# Sheet1.net
KiCad netlist of a schematic drawn in Altium Designer
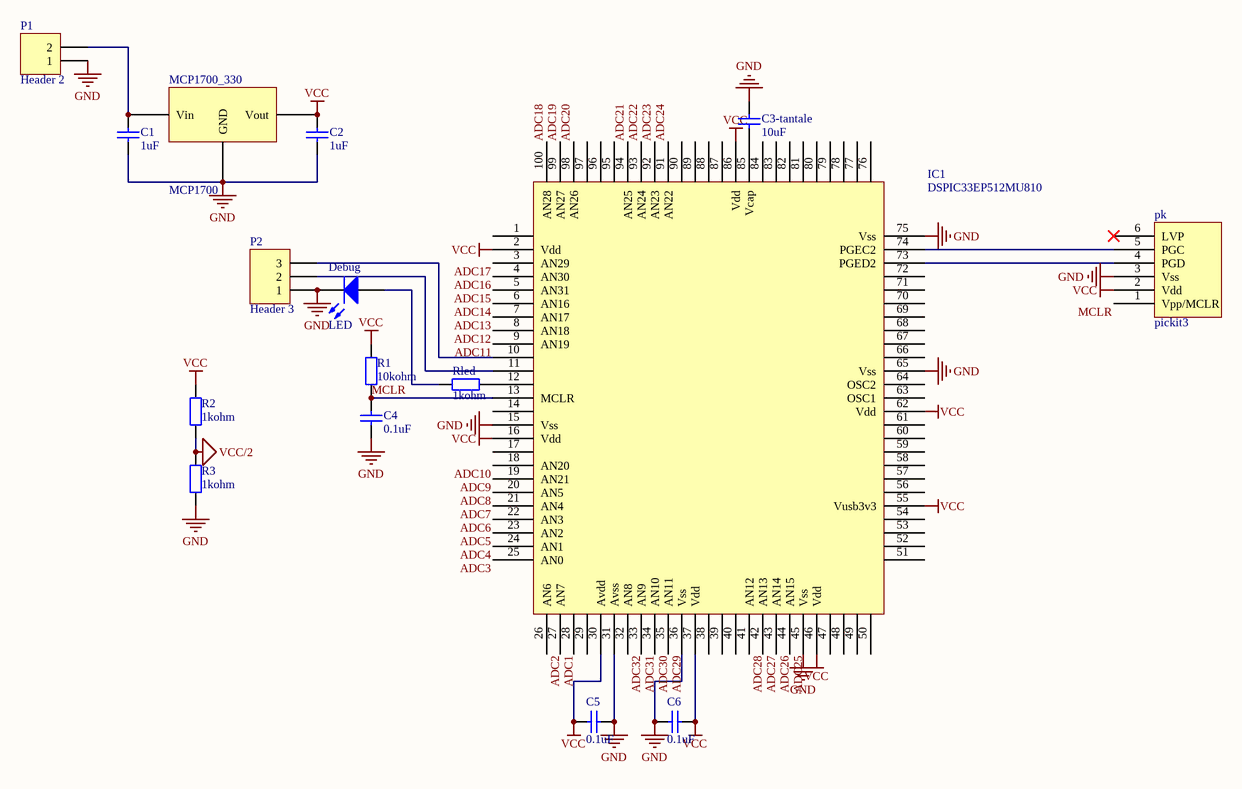
[diagram p0: Sheet1.SchDoc]

(export (version "E")
  (design (tool "Eeschema 10.0.6"))
  (components
    (comp (ref "C1")
      (value "1uF")
      (footprint "cms805 - mini")
      (libsource (lib "lib_Robotronik") (part "Capa"))
    )
    (comp (ref "C2")
      (value "1uF")
      (footprint "cms805 - mini")
      (libsource (lib "lib_Robotronik") (part "Capa"))
    )
    (comp (ref "C3-tantale")
      (value "10uF")
      (footprint "cms805")
      (libsource (lib "lib_Robotronik") (part "Capa"))
    )
    (comp (ref "C4")
      (value "0.1uF")
      (footprint "cms805 - mini")
      (libsource (lib "lib_Robotronik") (part "Capa"))
    )
    (comp (ref "C5")
      (value "0.1uF")
      (footprint "cms805 - mini")
      (libsource (lib "lib_Robotronik") (part "Capa"))
    )
    (comp (ref "C6")
      (value "0.1uF")
      (footprint "cms805 - mini")
      (libsource (lib "lib_Robotronik") (part "Capa"))
    )
    (comp (ref "Debug") (value "LED") (footprint "cms1206") (libsource (lib "lib_Robotronik") (part "LED")))
    (comp (ref "IC1")
      (value "DSPIC33EP512MU810")
      (footprint "TQFP100PF")
      (libsource (lib "lib_Robotronik") (part "DSPIC33EP512MU810"))
    )
    (comp (ref "MCP1700_330")
      (value "MCP1700")
      (footprint "SOT89")
      (libsource (lib "lib_Robotronik") (part "MCP1700"))
    )
    (comp (ref "P1")
      (value "Header 2")
      (footprint "HDR1X2")
      (description "Header, 2-Pin")
      (fields (field (name "PUBLISHER") "Altium Limited"))
      (libsource (lib "Miscellaneous Connectors") (part "Header 2"))
    )
    (comp (ref "P2")
      (value "Header 3")
      (footprint "HDR1X3")
      (description "Header, 3-Pin")
      (fields (field (name "PUBLISHER") "Altium Limited"))
      (libsource (lib "Miscellaneous Connectors") (part "Header 3"))
    )
    (comp (ref "pk")
      (value "pickit3")
      (footprint "pickit3")
      (libsource (lib "lib_Robotronik") (part "pickit3"))
    )
    (comp (ref "R1")
      (value "10kohm")
      (footprint "cms805 - mini")
      (libsource (lib "lib_Robotronik") (part "Resistance"))
    )
    (comp (ref "R2")
      (value "1kohm")
      (footprint "cms805 - mini")
      (libsource (lib "lib_Robotronik") (part "Resistance"))
    )
    (comp (ref "R3")
      (value "1kohm")
      (footprint "cms805 - mini")
      (libsource (lib "lib_Robotronik") (part "Resistance"))
    )
    (comp (ref "Rled") (value "1kohm") (footprint "cms805 - mini") (libsource (lib "") (part "Resistance_1")))
  )
  (nets
    (net (code "1") (name "/ADC1") (class "Default")
      (node (ref "IC1") (pin "27") (pinfunction "AN7_27") (pintype "passive"))
    )
    (net (code "2") (name "/ADC2") (class "Default")
      (node (ref "IC1") (pin "26") (pinfunction "AN6_26") (pintype "passive"))
    )
    (net (code "3") (name "/ADC3") (class "Default")
      (node (ref "IC1") (pin "25") (pinfunction "AN0_25") (pintype "passive"))
    )
    (net (code "4") (name "/ADC4") (class "Default")
      (node (ref "IC1") (pin "24") (pinfunction "AN1_24") (pintype "passive"))
    )
    (net (code "5") (name "/ADC5") (class "Default")
      (node (ref "IC1") (pin "23") (pinfunction "AN2_23") (pintype "passive"))
    )
    (net (code "6") (name "/ADC6") (class "Default")
      (node (ref "IC1") (pin "22") (pinfunction "AN3_22") (pintype "passive"))
    )
    (net (code "7") (name "/ADC7") (class "Default")
      (node (ref "IC1") (pin "21") (pinfunction "AN4_21") (pintype "passive"))
    )
    (net (code "8") (name "/ADC8") (class "Default")
      (node (ref "IC1") (pin "20") (pinfunction "AN5_20") (pintype "passive"))
    )
    (net (code "9") (name "/ADC9") (class "Default")
      (node (ref "IC1") (pin "19") (pinfunction "AN21_19") (pintype "passive"))
    )
    (net (code "10") (name "/ADC10") (class "Default")
      (node (ref "IC1") (pin "18") (pinfunction "AN20_18") (pintype "passive"))
    )
    (net (code "11") (name "/ADC11") (class "Default")
      (node (ref "IC1") (pin "9") (pinfunction "AN19_9") (pintype "passive"))
    )
    (net (code "12") (name "/ADC12") (class "Default")
      (node (ref "IC1") (pin "8") (pinfunction "AN18_8") (pintype "passive"))
    )
    (net (code "13") (name "/ADC13") (class "Default")
      (node (ref "IC1") (pin "7") (pinfunction "AN17_7") (pintype "passive"))
    )
    (net (code "14") (name "/ADC14") (class "Default")
      (node (ref "IC1") (pin "6") (pinfunction "AN16_6") (pintype "passive"))
    )
    (net (code "15") (name "/ADC15") (class "Default")
      (node (ref "IC1") (pin "5") (pinfunction "AN31_5") (pintype "passive"))
    )
    (net (code "16") (name "/ADC16") (class "Default")
      (node (ref "IC1") (pin "4") (pinfunction "AN30_4") (pintype "passive"))
    )
    (net (code "17") (name "/ADC17") (class "Default")
      (node (ref "IC1") (pin "3") (pinfunction "AN29_3") (pintype "passive"))
    )
    (net (code "18") (name "/ADC18") (class "Default")
      (node (ref "IC1") (pin "100") (pinfunction "AN28_100") (pintype "passive"))
    )
    (net (code "19") (name "/ADC19") (class "Default")
      (node (ref "IC1") (pin "99") (pinfunction "AN27_99") (pintype "passive"))
    )
    (net (code "20") (name "/ADC20") (class "Default")
      (node (ref "IC1") (pin "98") (pinfunction "AN26_98") (pintype "passive"))
    )
    (net (code "21") (name "/ADC21") (class "Default")
      (node (ref "IC1") (pin "94") (pinfunction "AN25_94") (pintype "passive"))
    )
    (net (code "22") (name "/ADC22") (class "Default")
      (node (ref "IC1") (pin "93") (pinfunction "AN24_93") (pintype "passive"))
    )
    (net (code "23") (name "/ADC23") (class "Default")
      (node (ref "IC1") (pin "92") (pinfunction "AN23_92") (pintype "passive"))
    )
    (net (code "24") (name "/ADC24") (class "Default")
      (node (ref "IC1") (pin "91") (pinfunction "AN22_91") (pintype "passive"))
    )
    (net (code "25") (name "/ADC25") (class "Default")
      (node (ref "IC1") (pin "44") (pinfunction "AN15_44") (pintype "passive"))
    )
    (net (code "26") (name "/ADC26") (class "Default")
      (node (ref "IC1") (pin "43") (pinfunction "AN14_43") (pintype "passive"))
    )
    (net (code "27") (name "/ADC27") (class "Default")
      (node (ref "IC1") (pin "42") (pinfunction "AN13_42") (pintype "passive"))
    )
    (net (code "28") (name "/ADC28") (class "Default")
      (node (ref "IC1") (pin "41") (pinfunction "AN12_41") (pintype "passive"))
    )
    (net (code "29") (name "/ADC29") (class "Default")
      (node (ref "IC1") (pin "35") (pinfunction "AN11_35") (pintype "passive"))
    )
    (net (code "30") (name "/ADC30") (class "Default")
      (node (ref "IC1") (pin "34") (pinfunction "AN10_34") (pintype "passive"))
    )
    (net (code "31") (name "/ADC31") (class "Default")
      (node (ref "IC1") (pin "33") (pinfunction "AN9_33") (pintype "passive"))
    )
    (net (code "32") (name "/ADC32") (class "Default")
      (node (ref "IC1") (pin "32") (pinfunction "AN8_32") (pintype "passive"))
    )
    (net (code "33") (name "/MCLR") (class "Default")
      (node (ref "C4") (pin "2") (pinfunction "2_2") (pintype "passive"))
      (node (ref "IC1") (pin "13") (pinfunction "MCLR_13") (pintype "passive"))
      (node (ref "R1") (pin "1") (pinfunction "1_1") (pintype "passive"))
      (node (ref "pk") (pin "1") (pinfunction "Vpp/MCLR_1") (pintype "passive"))
    )
    (net (code "34") (name "GND") (class "Default")
      (node (ref "C1") (pin "1") (pinfunction "1_1") (pintype "passive"))
      (node (ref "C2") (pin "1") (pinfunction "1_1") (pintype "passive"))
      (node (ref "C3-tantale") (pin "2") (pinfunction "2_2") (pintype "passive"))
      (node (ref "C4") (pin "1") (pinfunction "1_1") (pintype "passive"))
      (node (ref "C5") (pin "1") (pinfunction "1_1") (pintype "passive"))
      (node (ref "C6") (pin "2") (pinfunction "2_2") (pintype "passive"))
      (node (ref "Debug") (pin "2") (pinfunction "K_2") (pintype "passive"))
      (node (ref "IC1") (pin "15") (pinfunction "Vss_15") (pintype "passive"))
      (node (ref "IC1") (pin "31") (pinfunction "Avss_31") (pintype "passive"))
      (node (ref "IC1") (pin "36") (pinfunction "Vss_36") (pintype "passive"))
      (node (ref "IC1") (pin "45") (pinfunction "Vss_45") (pintype "passive"))
      (node (ref "IC1") (pin "65") (pinfunction "Vss_65") (pintype "passive"))
      (node (ref "IC1") (pin "75") (pinfunction "Vss_75") (pintype "passive"))
      (node (ref "MCP1700_330") (pin "1") (pinfunction "GND_1") (pintype "passive"))
      (node (ref "P1") (pin "1") (pinfunction "1_1") (pintype "passive"))
      (node (ref "P2") (pin "1") (pinfunction "1_1") (pintype "passive"))
      (node (ref "R3") (pin "1") (pinfunction "1_1") (pintype "passive"))
      (node (ref "pk") (pin "3") (pinfunction "Vss_3") (pintype "passive"))
    )
    (net (code "35") (name "Net-(Debug-A)") (class "Default")
      (node (ref "Debug") (pin "1") (pinfunction "A_1") (pintype "passive"))
      (node (ref "Rled") (pin "2") (pinfunction "2_2") (pintype "passive"))
    )
    (net (code "36") (name "Net-(IC1-PGEC2)") (class "Default")
      (node (ref "IC1") (pin "74") (pinfunction "PGEC2_74") (pintype "passive"))
      (node (ref "pk") (pin "5") (pinfunction "PGC_5") (pintype "passive"))
    )
    (net (code "37") (name "Net-(IC1-PGED2)") (class "Default")
      (node (ref "IC1") (pin "73") (pinfunction "PGED2_73") (pintype "passive"))
      (node (ref "pk") (pin "4") (pinfunction "PGD_4") (pintype "passive"))
    )
    (net (code "38") (name "Net-(IC1-Pad10)") (class "Default")
      (node (ref "IC1") (pin "10") (pintype "passive"))
      (node (ref "P2") (pin "3") (pinfunction "3_3") (pintype "passive"))
    )
    (net (code "39") (name "Net-(IC1-Pad11)") (class "Default")
      (node (ref "IC1") (pin "11") (pintype "passive"))
      (node (ref "P2") (pin "2") (pinfunction "2_2") (pintype "passive"))
    )
    (net (code "40") (name "Net-(IC1-Pad12)") (class "Default")
      (node (ref "IC1") (pin "12") (pintype "passive"))
      (node (ref "Rled") (pin "1") (pinfunction "1_1") (pintype "passive"))
    )
    (net (code "41") (name "Net-(IC1-Vcap)") (class "Default")
      (node (ref "C3-tantale") (pin "1") (pinfunction "1_1") (pintype "passive"))
      (node (ref "IC1") (pin "85") (pinfunction "Vcap_85") (pintype "passive"))
    )
    (net (code "42") (name "Net-(MCP1700_330-Vin)") (class "Default")
      (node (ref "C1") (pin "2") (pinfunction "2_2") (pintype "passive"))
      (node (ref "MCP1700_330") (pin "2") (pinfunction "Vin_2") (pintype "passive"))
      (node (ref "P1") (pin "2") (pinfunction "2_2") (pintype "passive"))
    )
    (net (code "43") (name "VCC") (class "Default")
      (node (ref "C2") (pin "2") (pinfunction "2_2") (pintype "passive"))
      (node (ref "C5") (pin "2") (pinfunction "2_2") (pintype "passive"))
      (node (ref "C6") (pin "1") (pinfunction "1_1") (pintype "passive"))
      (node (ref "IC1") (pin "16") (pinfunction "Vdd_16") (pintype "passive"))
      (node (ref "IC1") (pin "2") (pinfunction "Vdd_2") (pintype "passive"))
      (node (ref "IC1") (pin "30") (pinfunction "Avdd_30") (pintype "passive"))
      (node (ref "IC1") (pin "37") (pinfunction "Vdd_37") (pintype "passive"))
      (node (ref "IC1") (pin "46") (pinfunction "Vdd_46") (pintype "passive"))
      (node (ref "IC1") (pin "55") (pinfunction "Vusb3v3_55") (pintype "passive"))
      (node (ref "IC1") (pin "62") (pinfunction "Vdd_62") (pintype "passive"))
      (node (ref "IC1") (pin "86") (pinfunction "Vdd_86") (pintype "passive"))
      (node (ref "MCP1700_330") (pin "3") (pinfunction "Vout_3") (pintype "passive"))
      (node (ref "R1") (pin "2") (pinfunction "2_2") (pintype "passive"))
      (node (ref "R2") (pin "2") (pinfunction "2_2") (pintype "passive"))
      (node (ref "pk") (pin "2") (pinfunction "Vdd_2") (pintype "passive"))
    )
    (net (code "44") (name "VCC{slash}2") (class "Default")
      (node (ref "R2") (pin "1") (pinfunction "1_1") (pintype "passive"))
      (node (ref "R3") (pin "2") (pinfunction "2_2") (pintype "passive"))
    )
    (net (code "45") (name "unconnected-(IC1-OSC1-Pad63)") (class "Default")
      (node (ref "IC1") (pin "63") (pinfunction "OSC1_63") (pintype "passive"))
    )
    (net (code "46") (name "unconnected-(IC1-OSC2-Pad64)") (class "Default")
      (node (ref "IC1") (pin "64") (pinfunction "OSC2_64") (pintype "passive"))
    )
    (net (code "47") (name "unconnected-(IC1-Pad1)") (class "Default")
      (node (ref "IC1") (pin "1") (pintype "passive"))
    )
    (net (code "48") (name "unconnected-(IC1-Pad14)") (class "Default")
      (node (ref "IC1") (pin "14") (pintype "passive"))
    )
    (net (code "49") (name "unconnected-(IC1-Pad17)") (class "Default")
      (node (ref "IC1") (pin "17") (pintype "passive"))
    )
    (net (code "50") (name "unconnected-(IC1-Pad28)") (class "Default")
      (node (ref "IC1") (pin "28") (pinfunction "28_28") (pintype "passive"))
    )
    (net (code "51") (name "unconnected-(IC1-Pad29)") (class "Default")
      (node (ref "IC1") (pin "29") (pinfunction "29_29") (pintype "passive"))
    )
    (net (code "52") (name "unconnected-(IC1-Pad38)") (class "Default")
      (node (ref "IC1") (pin "38") (pinfunction "38_38") (pintype "passive"))
    )
    (net (code "53") (name "unconnected-(IC1-Pad39)") (class "Default")
      (node (ref "IC1") (pin "39") (pinfunction "39_39") (pintype "passive"))
    )
    (net (code "54") (name "unconnected-(IC1-Pad40)") (class "Default")
      (node (ref "IC1") (pin "40") (pinfunction "40_40") (pintype "passive"))
    )
    (net (code "55") (name "unconnected-(IC1-Pad47)") (class "Default")
      (node (ref "IC1") (pin "47") (pinfunction "47_47") (pintype "passive"))
    )
    (net (code "56") (name "unconnected-(IC1-Pad48)") (class "Default")
      (node (ref "IC1") (pin "48") (pinfunction "48_48") (pintype "passive"))
    )
    (net (code "57") (name "unconnected-(IC1-Pad49)") (class "Default")
      (node (ref "IC1") (pin "49") (pinfunction "49_49") (pintype "passive"))
    )
    (net (code "58") (name "unconnected-(IC1-Pad50)") (class "Default")
      (node (ref "IC1") (pin "50") (pinfunction "50_50") (pintype "passive"))
    )
    (net (code "59") (name "unconnected-(IC1-Pad51)") (class "Default")
      (node (ref "IC1") (pin "51") (pinfunction "51_51") (pintype "passive"))
    )
    (net (code "60") (name "unconnected-(IC1-Pad52)") (class "Default")
      (node (ref "IC1") (pin "52") (pinfunction "52_52") (pintype "passive"))
    )
    (net (code "61") (name "unconnected-(IC1-Pad53)") (class "Default")
      (node (ref "IC1") (pin "53") (pinfunction "53_53") (pintype "passive"))
    )
    (net (code "62") (name "unconnected-(IC1-Pad54)") (class "Default")
      (node (ref "IC1") (pin "54") (pinfunction "54_54") (pintype "passive"))
    )
    (net (code "63") (name "unconnected-(IC1-Pad56)") (class "Default")
      (node (ref "IC1") (pin "56") (pinfunction "56_56") (pintype "passive"))
    )
    (net (code "64") (name "unconnected-(IC1-Pad57)") (class "Default")
      (node (ref "IC1") (pin "57") (pinfunction "57_57") (pintype "passive"))
    )
    (net (code "65") (name "unconnected-(IC1-Pad58)") (class "Default")
      (node (ref "IC1") (pin "58") (pinfunction "58_58") (pintype "passive"))
    )
    (net (code "66") (name "unconnected-(IC1-Pad59)") (class "Default")
      (node (ref "IC1") (pin "59") (pinfunction "59_59") (pintype "passive"))
    )
    (net (code "67") (name "unconnected-(IC1-Pad60)") (class "Default")
      (node (ref "IC1") (pin "60") (pinfunction "60_60") (pintype "passive"))
    )
    (net (code "68") (name "unconnected-(IC1-Pad61)") (class "Default")
      (node (ref "IC1") (pin "61") (pinfunction "61_61") (pintype "passive"))
    )
    (net (code "69") (name "unconnected-(IC1-Pad66)") (class "Default")
      (node (ref "IC1") (pin "66") (pinfunction "66_66") (pintype "passive"))
    )
    (net (code "70") (name "unconnected-(IC1-Pad67)") (class "Default")
      (node (ref "IC1") (pin "67") (pinfunction "67_67") (pintype "passive"))
    )
    (net (code "71") (name "unconnected-(IC1-Pad68)") (class "Default")
      (node (ref "IC1") (pin "68") (pinfunction "68_68") (pintype "passive"))
    )
    (net (code "72") (name "unconnected-(IC1-Pad69)") (class "Default")
      (node (ref "IC1") (pin "69") (pinfunction "69_69") (pintype "passive"))
    )
    (net (code "73") (name "unconnected-(IC1-Pad70)") (class "Default")
      (node (ref "IC1") (pin "70") (pinfunction "70_70") (pintype "passive"))
    )
    (net (code "74") (name "unconnected-(IC1-Pad71)") (class "Default")
      (node (ref "IC1") (pin "71") (pinfunction "71_71") (pintype "passive"))
    )
    (net (code "75") (name "unconnected-(IC1-Pad72)") (class "Default")
      (node (ref "IC1") (pin "72") (pinfunction "72_72") (pintype "passive"))
    )
    (net (code "76") (name "unconnected-(IC1-Pad76)") (class "Default")
      (node (ref "IC1") (pin "76") (pinfunction "76_76") (pintype "passive"))
    )
    (net (code "77") (name "unconnected-(IC1-Pad77)") (class "Default")
      (node (ref "IC1") (pin "77") (pinfunction "77_77") (pintype "passive"))
    )
    (net (code "78") (name "unconnected-(IC1-Pad78)") (class "Default")
      (node (ref "IC1") (pin "78") (pinfunction "78_78") (pintype "passive"))
    )
    (net (code "79") (name "unconnected-(IC1-Pad79)") (class "Default")
      (node (ref "IC1") (pin "79") (pinfunction "79_79") (pintype "passive"))
    )
    (net (code "80") (name "unconnected-(IC1-Pad80)") (class "Default")
      (node (ref "IC1") (pin "80") (pinfunction "80_80") (pintype "passive"))
    )
    (net (code "81") (name "unconnected-(IC1-Pad81)") (class "Default")
      (node (ref "IC1") (pin "81") (pinfunction "81_81") (pintype "passive"))
    )
    (net (code "82") (name "unconnected-(IC1-Pad82)") (class "Default")
      (node (ref "IC1") (pin "82") (pinfunction "82_82") (pintype "passive"))
    )
    (net (code "83") (name "unconnected-(IC1-Pad83)") (class "Default")
      (node (ref "IC1") (pin "83") (pinfunction "83_83") (pintype "passive"))
    )
    (net (code "84") (name "unconnected-(IC1-Pad84)") (class "Default")
      (node (ref "IC1") (pin "84") (pinfunction "84_84") (pintype "passive"))
    )
    (net (code "85") (name "unconnected-(IC1-Pad87)") (class "Default")
      (node (ref "IC1") (pin "87") (pinfunction "87_87") (pintype "passive"))
    )
    (net (code "86") (name "unconnected-(IC1-Pad88)") (class "Default")
      (node (ref "IC1") (pin "88") (pinfunction "88_88") (pintype "passive"))
    )
    (net (code "87") (name "unconnected-(IC1-Pad89)") (class "Default")
      (node (ref "IC1") (pin "89") (pinfunction "89_89") (pintype "passive"))
    )
    (net (code "88") (name "unconnected-(IC1-Pad90)") (class "Default")
      (node (ref "IC1") (pin "90") (pinfunction "90_90") (pintype "passive"))
    )
    (net (code "89") (name "unconnected-(IC1-Pad95)") (class "Default")
      (node (ref "IC1") (pin "95") (pinfunction "95_95") (pintype "passive"))
    )
    (net (code "90") (name "unconnected-(IC1-Pad96)") (class "Default")
      (node (ref "IC1") (pin "96") (pinfunction "96_96") (pintype "passive"))
    )
    (net (code "91") (name "unconnected-(IC1-Pad97)") (class "Default")
      (node (ref "IC1") (pin "97") (pinfunction "97_97") (pintype "passive"))
    )
    (net (code "92") (name "unconnected-(pk-LVP-Pad6)") (class "Default")
      (node (ref "pk") (pin "6") (pinfunction "LVP_6") (pintype "passive+no_connect"))
    )
  )
)
